# main.net
KiCad netlist of a schematic drawn in EAGLE
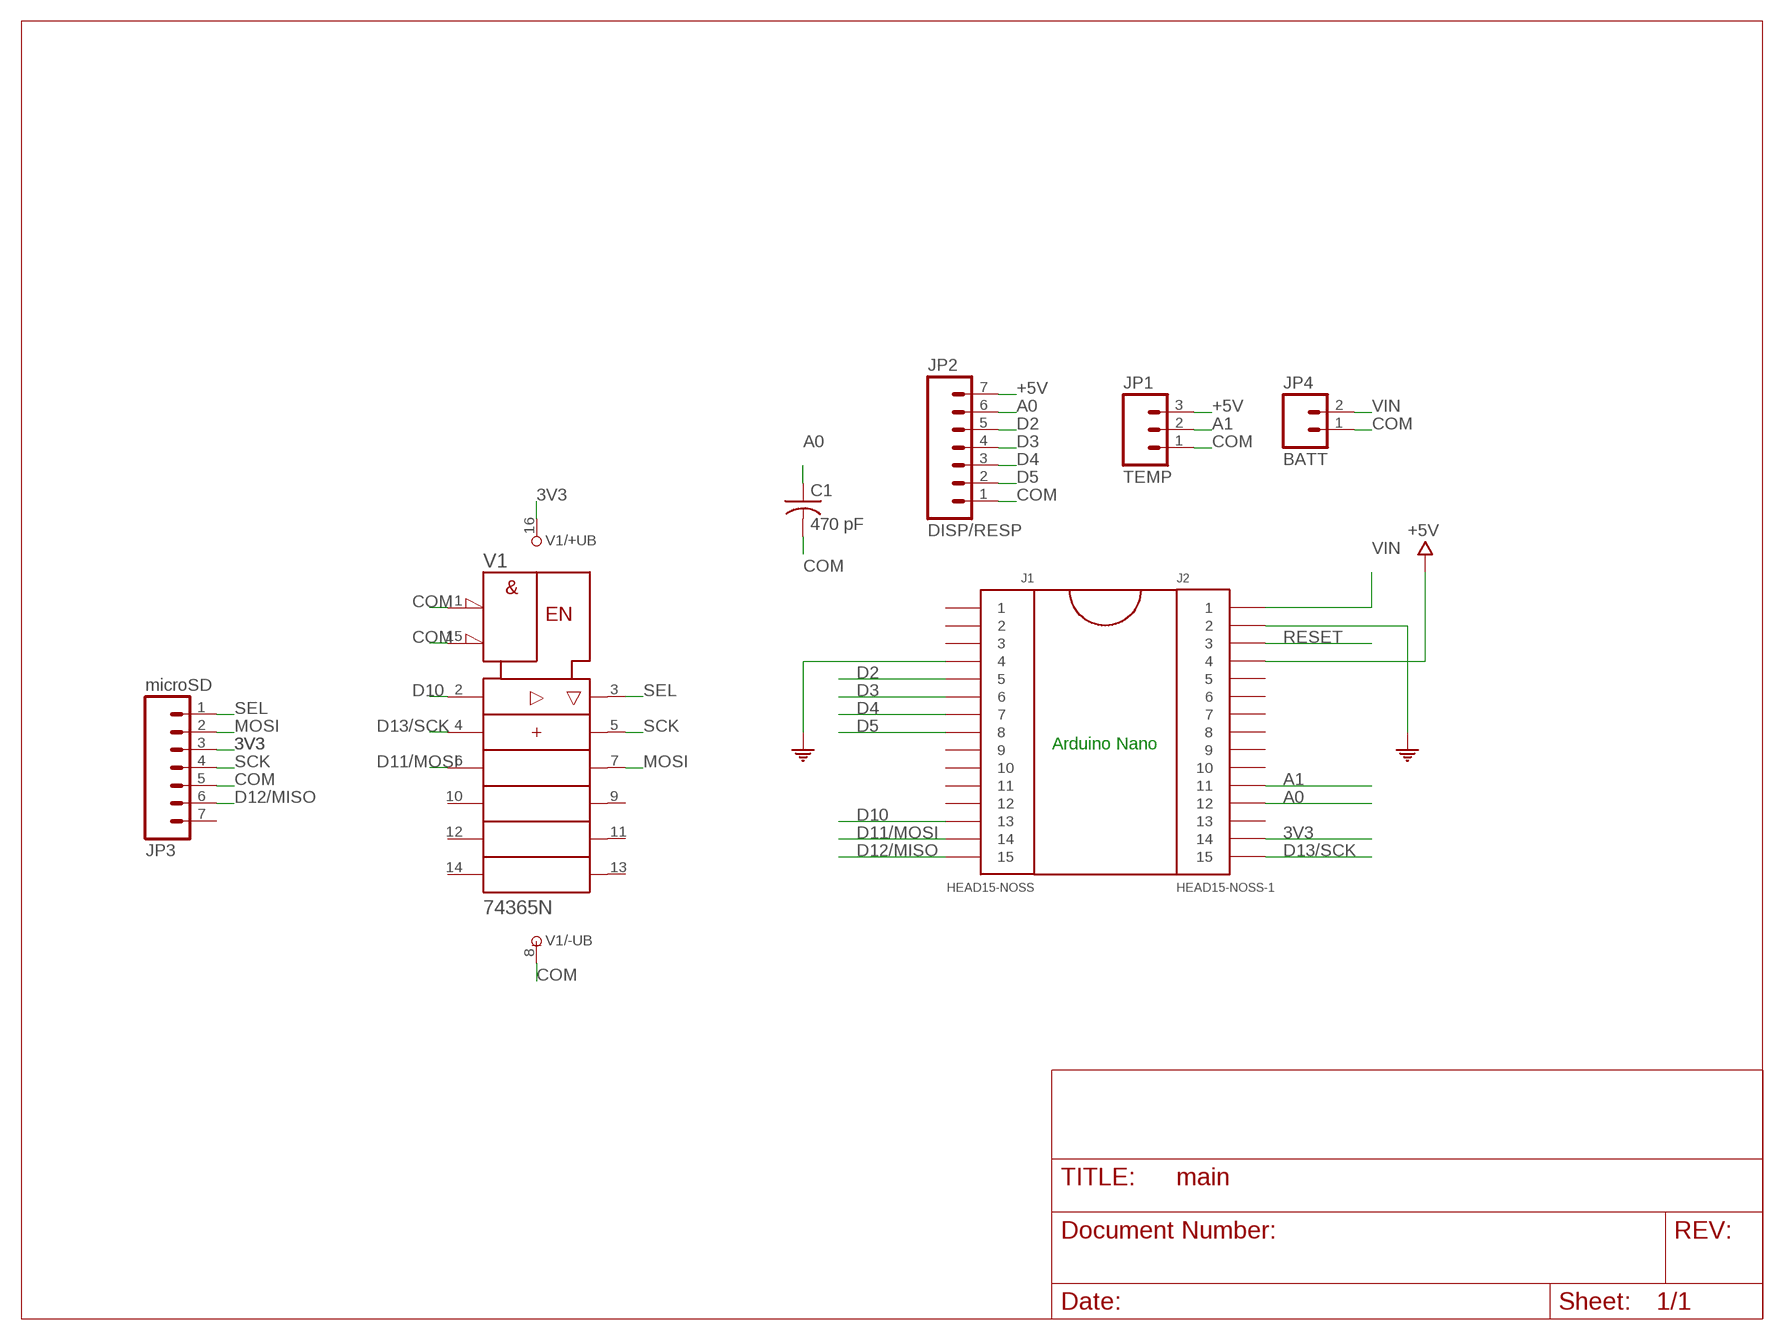
[diagram p0: schematic, sheet 1]

(export (version "E")
  (design (tool "Eeschema 10.0.6"))
  (components
    (comp (ref "C1")
      (value "470 pF")
      (footprint "eagle-import:C050-024X044")
      (libsource (lib "eagle-import") (part "C-US050-024X044"))
    )
    (comp (ref "J1")
      (value "HEAD15-NOSS")
      (footprint "eagle-import:HEAD15-NOSS")
      (libsource (lib "eagle-import") (part "HEAD15-NOSS"))
    )
    (comp (ref "J2")
      (value "HEAD15-NOSS-1")
      (footprint "eagle-import:HEAD15-NOSS-1")
      (libsource (lib "eagle-import") (part "HEAD15-NOSS-1"))
    )
    (comp (ref "JP1")
      (value "TEMP")
      (footprint "eagle-import:1X03")
      (libsource (lib "eagle-import") (part "M03PTH"))
    )
    (comp (ref "JP2")
      (value "DISP/RESP")
      (footprint "eagle-import:1X07")
      (libsource (lib "eagle-import") (part "M07"))
    )
    (comp (ref "JP3")
      (value "microSD")
      (footprint "eagle-import:1X07")
      (libsource (lib "eagle-import") (part "M07"))
    )
    (comp (ref "JP4")
      (value "BATT")
      (footprint "eagle-import:1X02")
      (libsource (lib "eagle-import") (part "M02PTH"))
    )
    (comp (ref "V1")
      (value "74365N")
      (footprint "eagle-import:DIL16")
      (libsource (lib "eagle-import") (part "74365N"))
    )
  )
  (nets
    (net (code "1") (name "+5V") (class "Default")
      (node (ref "J2") (pin "4") (pinfunction "4_4") (pintype "passive"))
      (node (ref "JP1") (pin "3") (pinfunction "3_3") (pintype "passive"))
      (node (ref "JP2") (pin "7") (pinfunction "7_7") (pintype "passive"))
    )
    (net (code "2") (name "/3V3") (class "Default")
      (node (ref "J2") (pin "14") (pinfunction "14_14") (pintype "passive"))
      (node (ref "JP3") (pin "3") (pinfunction "3_3") (pintype "passive"))
      (node (ref "V1") (pin "16") (pinfunction "+UB_16") (pintype "power_in"))
    )
    (net (code "3") (name "/A0") (class "Default")
      (node (ref "C1") (pin "1") (pinfunction "1_1") (pintype "passive"))
      (node (ref "J2") (pin "12") (pinfunction "12_12") (pintype "passive"))
      (node (ref "JP2") (pin "6") (pinfunction "6_6") (pintype "passive"))
    )
    (net (code "4") (name "/A1") (class "Default")
      (node (ref "J2") (pin "11") (pinfunction "11_11") (pintype "passive"))
      (node (ref "JP1") (pin "2") (pinfunction "2_2") (pintype "passive"))
    )
    (net (code "5") (name "/D2") (class "Default")
      (node (ref "J1") (pin "5") (pinfunction "5_5") (pintype "passive"))
      (node (ref "JP2") (pin "5") (pinfunction "5_5") (pintype "passive"))
    )
    (net (code "6") (name "/D3") (class "Default")
      (node (ref "J1") (pin "6") (pinfunction "6_6") (pintype "passive"))
      (node (ref "JP2") (pin "4") (pinfunction "4_4") (pintype "passive"))
    )
    (net (code "7") (name "/D4") (class "Default")
      (node (ref "J1") (pin "7") (pinfunction "7_7") (pintype "passive"))
      (node (ref "JP2") (pin "3") (pinfunction "3_3") (pintype "passive"))
    )
    (net (code "8") (name "/D5") (class "Default")
      (node (ref "J1") (pin "8") (pinfunction "8_8") (pintype "passive"))
      (node (ref "JP2") (pin "2") (pinfunction "2_2") (pintype "passive"))
    )
    (net (code "9") (name "/D10") (class "Default")
      (node (ref "J1") (pin "13") (pinfunction "13_13") (pintype "passive"))
      (node (ref "V1") (pin "2") (pinfunction "A1_2") (pintype "input"))
    )
    (net (code "10") (name "/D11{slash}MOSI") (class "Default")
      (node (ref "J1") (pin "14") (pinfunction "14_14") (pintype "passive"))
      (node (ref "V1") (pin "6") (pinfunction "A3_6") (pintype "input"))
    )
    (net (code "11") (name "/D12{slash}MISO") (class "Default")
      (node (ref "J1") (pin "15") (pinfunction "15_15") (pintype "passive"))
      (node (ref "JP3") (pin "6") (pinfunction "6_6") (pintype "passive"))
    )
    (net (code "12") (name "/D13{slash}SCK") (class "Default")
      (node (ref "J2") (pin "15") (pinfunction "15_15") (pintype "passive"))
      (node (ref "V1") (pin "4") (pinfunction "A2_4") (pintype "input"))
    )
    (net (code "13") (name "/MOSI") (class "Default")
      (node (ref "JP3") (pin "2") (pinfunction "2_2") (pintype "passive"))
      (node (ref "V1") (pin "7") (pinfunction "Y3_7") (pintype "tri_state"))
    )
    (net (code "14") (name "/RESET") (class "Default")
      (node (ref "J2") (pin "3") (pinfunction "3_3") (pintype "passive"))
    )
    (net (code "15") (name "/SCK") (class "Default")
      (node (ref "JP3") (pin "4") (pinfunction "4_4") (pintype "passive"))
      (node (ref "V1") (pin "5") (pinfunction "Y2_5") (pintype "tri_state"))
    )
    (net (code "16") (name "/SEL") (class "Default")
      (node (ref "JP3") (pin "1") (pinfunction "1_1") (pintype "passive"))
      (node (ref "V1") (pin "3") (pinfunction "Y1_3") (pintype "tri_state"))
    )
    (net (code "17") (name "/VIN") (class "Default")
      (node (ref "J2") (pin "1") (pinfunction "1_1") (pintype "passive"))
      (node (ref "JP4") (pin "2") (pinfunction "2_2") (pintype "passive"))
    )
    (net (code "18") (name "COM") (class "Default")
      (node (ref "C1") (pin "2") (pinfunction "2_2") (pintype "passive"))
      (node (ref "J1") (pin "4") (pinfunction "4_4") (pintype "passive"))
      (node (ref "J2") (pin "2") (pinfunction "2_2") (pintype "passive"))
      (node (ref "JP1") (pin "1") (pinfunction "1_1") (pintype "passive"))
      (node (ref "JP2") (pin "1") (pinfunction "1_1") (pintype "passive"))
      (node (ref "JP3") (pin "5") (pinfunction "5_5") (pintype "passive"))
      (node (ref "JP4") (pin "1") (pinfunction "1_1") (pintype "passive"))
      (node (ref "V1") (pin "1") (pinfunction "~{G1}_1") (pintype "input"))
      (node (ref "V1") (pin "15") (pinfunction "~{G2}_15") (pintype "input"))
      (node (ref "V1") (pin "8") (pinfunction "-UB_8") (pintype "power_in"))
    )
    (net (code "19") (name "unconnected-(J1-Pad1)") (class "Default")
      (node (ref "J1") (pin "1") (pinfunction "1_1") (pintype "passive"))
    )
    (net (code "20") (name "unconnected-(J1-Pad2)") (class "Default")
      (node (ref "J1") (pin "2") (pinfunction "2_2") (pintype "passive"))
    )
    (net (code "21") (name "unconnected-(J1-Pad3)") (class "Default")
      (node (ref "J1") (pin "3") (pinfunction "3_3") (pintype "passive"))
    )
    (net (code "22") (name "unconnected-(J1-Pad9)") (class "Default")
      (node (ref "J1") (pin "9") (pinfunction "9_9") (pintype "passive"))
    )
    (net (code "23") (name "unconnected-(J1-Pad10)") (class "Default")
      (node (ref "J1") (pin "10") (pinfunction "10_10") (pintype "passive"))
    )
    (net (code "24") (name "unconnected-(J1-Pad11)") (class "Default")
      (node (ref "J1") (pin "11") (pinfunction "11_11") (pintype "passive"))
    )
    (net (code "25") (name "unconnected-(J1-Pad12)") (class "Default")
      (node (ref "J1") (pin "12") (pinfunction "12_12") (pintype "passive"))
    )
    (net (code "26") (name "unconnected-(J2-Pad5)") (class "Default")
      (node (ref "J2") (pin "5") (pinfunction "5_5") (pintype "passive"))
    )
    (net (code "27") (name "unconnected-(J2-Pad6)") (class "Default")
      (node (ref "J2") (pin "6") (pinfunction "6_6") (pintype "passive"))
    )
    (net (code "28") (name "unconnected-(J2-Pad7)") (class "Default")
      (node (ref "J2") (pin "7") (pinfunction "7_7") (pintype "passive"))
    )
    (net (code "29") (name "unconnected-(J2-Pad8)") (class "Default")
      (node (ref "J2") (pin "8") (pinfunction "8_8") (pintype "passive"))
    )
    (net (code "30") (name "unconnected-(J2-Pad9)") (class "Default")
      (node (ref "J2") (pin "9") (pinfunction "9_9") (pintype "passive"))
    )
    (net (code "31") (name "unconnected-(J2-Pad10)") (class "Default")
      (node (ref "J2") (pin "10") (pinfunction "10_10") (pintype "passive"))
    )
    (net (code "32") (name "unconnected-(J2-Pad13)") (class "Default")
      (node (ref "J2") (pin "13") (pinfunction "13_13") (pintype "passive"))
    )
    (net (code "33") (name "unconnected-(JP3-Pad7)") (class "Default")
      (node (ref "JP3") (pin "7") (pinfunction "7_7") (pintype "passive"))
    )
    (net (code "34") (name "unconnected-(V1C-A4-Pad10)") (class "Default")
      (node (ref "V1") (pin "10") (pinfunction "A4_10") (pintype "input"))
    )
    (net (code "35") (name "unconnected-(V1C-A5-Pad12)") (class "Default")
      (node (ref "V1") (pin "12") (pinfunction "A5_12") (pintype "input"))
    )
    (net (code "36") (name "unconnected-(V1C-A6-Pad14)") (class "Default")
      (node (ref "V1") (pin "14") (pinfunction "A6_14") (pintype "input"))
    )
    (net (code "37") (name "unconnected-(V1C-Y4-Pad9)") (class "Default")
      (node (ref "V1") (pin "9") (pinfunction "Y4_9") (pintype "tri_state"))
    )
    (net (code "38") (name "unconnected-(V1C-Y5-Pad11)") (class "Default")
      (node (ref "V1") (pin "11") (pinfunction "Y5_11") (pintype "tri_state"))
    )
    (net (code "39") (name "unconnected-(V1C-Y6-Pad13)") (class "Default")
      (node (ref "V1") (pin "13") (pinfunction "Y6_13") (pintype "tri_state"))
    )
  )
)
